# Final.net
KiCad netlist of a schematic drawn in EAGLE
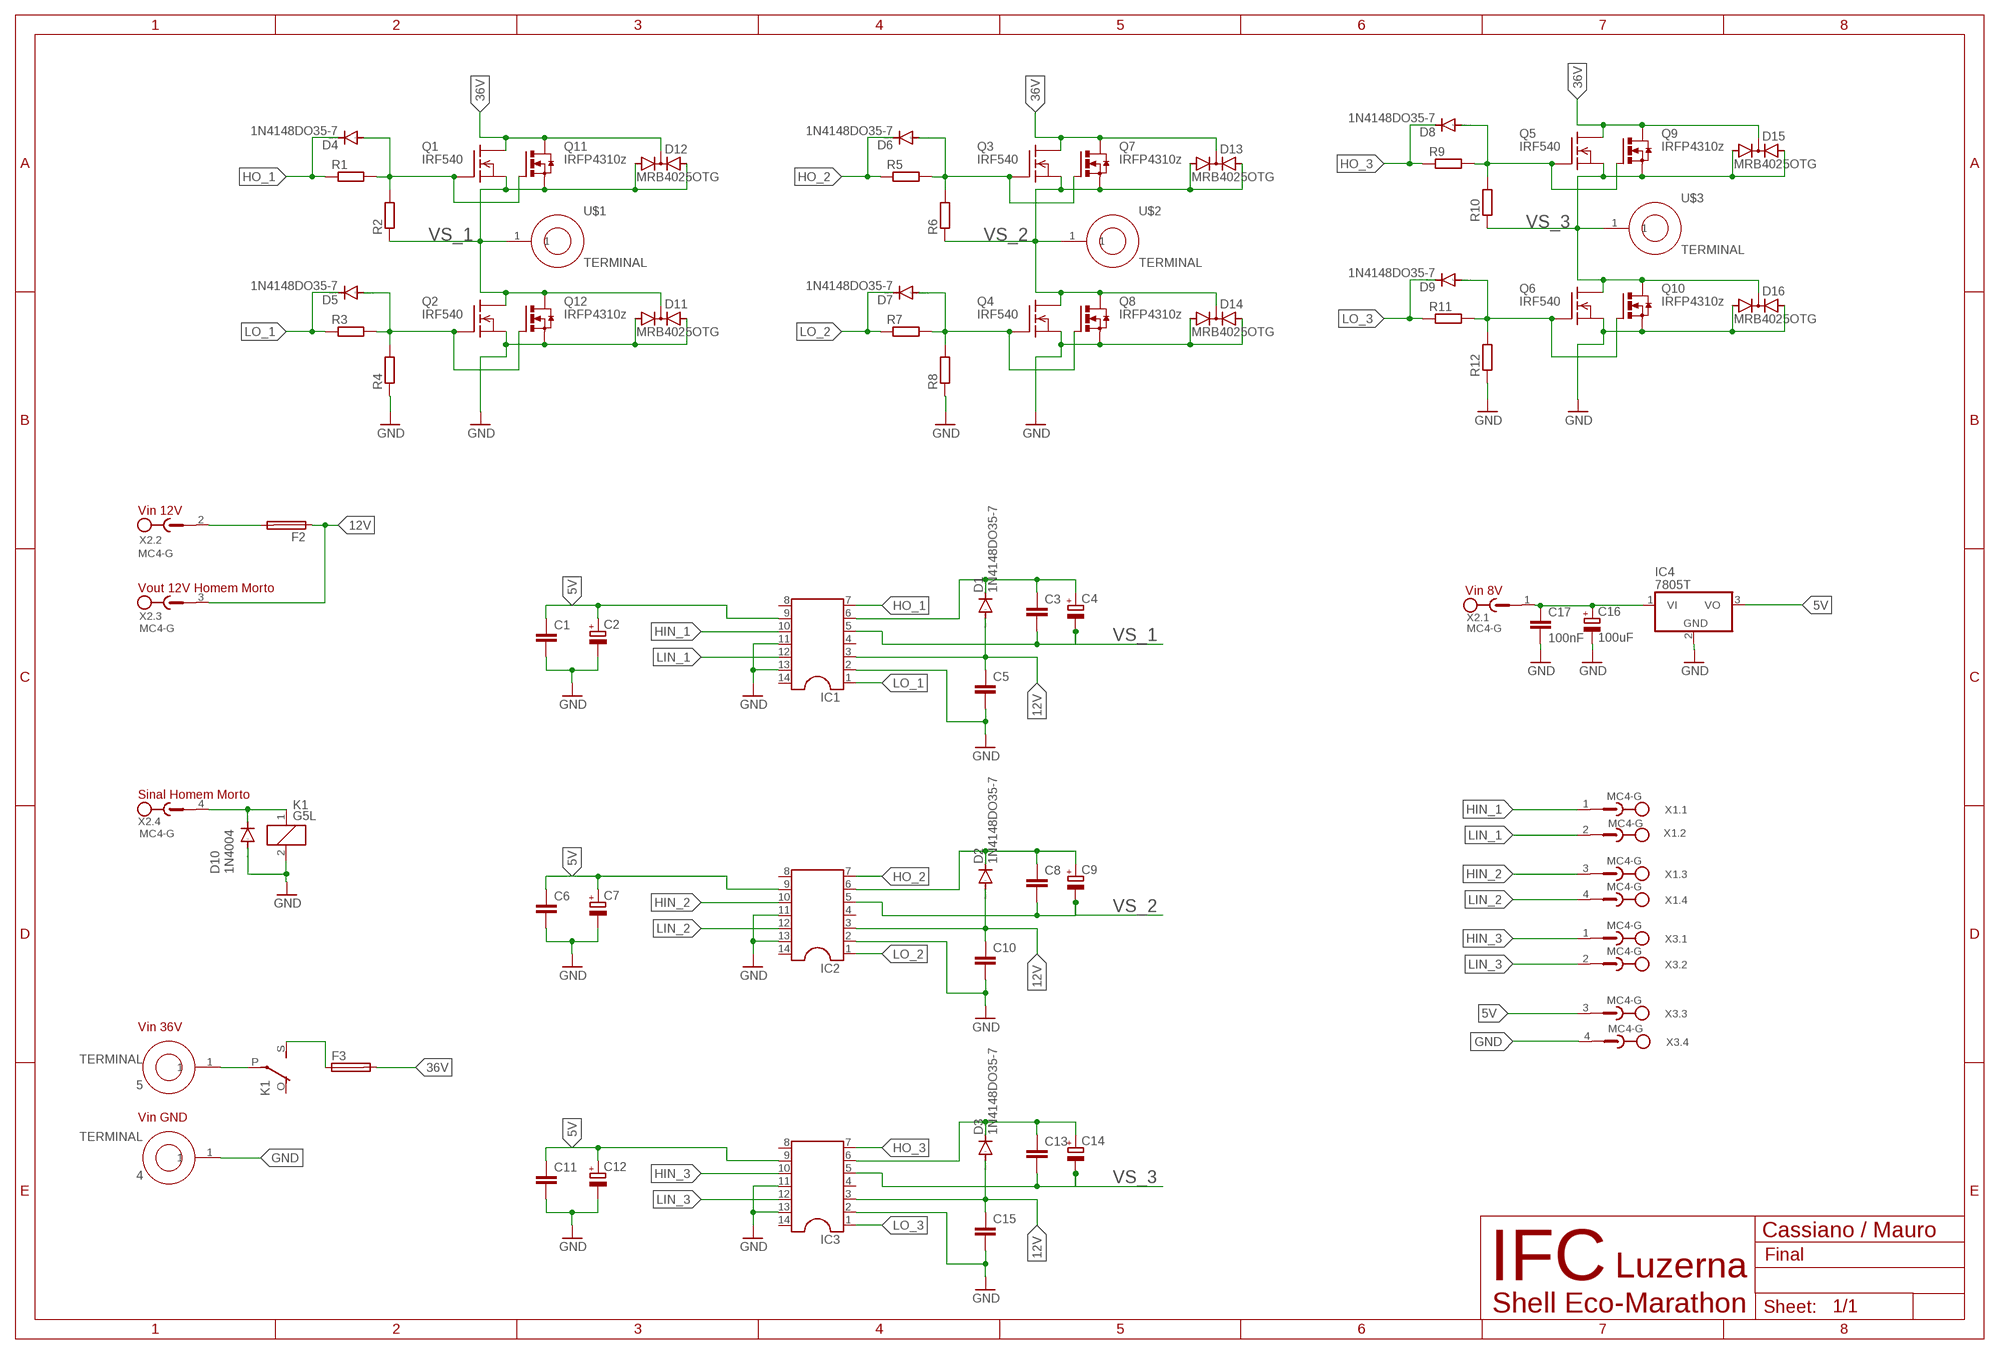
[diagram p0: schematic, sheet 1]

(export (version "E")
  (design (tool "Eeschema 10.0.6"))
  (components
    (comp (ref "4")
      (value "TERMINAL")
      (footprint "eagle-import:TERMINAL")
      (libsource (lib "eagle-import") (part "TERMINAL"))
    )
    (comp (ref "5")
      (value "TERMINAL")
      (footprint "eagle-import:TERMINAL")
      (libsource (lib "eagle-import") (part "TERMINAL"))
    )
    (comp (ref "C1")
      (value "C-EU050-045X075")
      (footprint "eagle-import:C050-045X075")
      (libsource (lib "eagle-import") (part "C-EU050-045X075"))
    )
    (comp (ref "C2")
      (value "CPOL-EUE2.5-7")
      (footprint "eagle-import:E2,5-7")
      (libsource (lib "eagle-import") (part "CPOL-EUE2.5-7"))
    )
    (comp (ref "C3")
      (value "C-EU050-025X075")
      (footprint "eagle-import:C050-025X075")
      (libsource (lib "eagle-import") (part "C-EU050-025X075"))
    )
    (comp (ref "C4")
      (value "CPOL-EUE2.5-7")
      (footprint "eagle-import:E2,5-7")
      (libsource (lib "eagle-import") (part "CPOL-EUE2.5-7"))
    )
    (comp (ref "C5")
      (value "C-EU050-025X075")
      (footprint "eagle-import:C050-025X075")
      (libsource (lib "eagle-import") (part "C-EU050-025X075"))
    )
    (comp (ref "C6")
      (value "C-EU050-045X075")
      (footprint "eagle-import:C050-045X075")
      (libsource (lib "eagle-import") (part "C-EU050-045X075"))
    )
    (comp (ref "C7")
      (value "CPOL-EUE2.5-7")
      (footprint "eagle-import:E2,5-7")
      (libsource (lib "eagle-import") (part "CPOL-EUE2.5-7"))
    )
    (comp (ref "C8")
      (value "C-EU050-025X075")
      (footprint "eagle-import:C050-025X075")
      (libsource (lib "eagle-import") (part "C-EU050-025X075"))
    )
    (comp (ref "C9")
      (value "CPOL-EUE2.5-7")
      (footprint "eagle-import:E2,5-7")
      (libsource (lib "eagle-import") (part "CPOL-EUE2.5-7"))
    )
    (comp (ref "C10")
      (value "C-EU050-025X075")
      (footprint "eagle-import:C050-025X075")
      (libsource (lib "eagle-import") (part "C-EU050-025X075"))
    )
    (comp (ref "C11")
      (value "C-EU050-045X075")
      (footprint "eagle-import:C050-045X075")
      (libsource (lib "eagle-import") (part "C-EU050-045X075"))
    )
    (comp (ref "C12")
      (value "CPOL-EUE2.5-7")
      (footprint "eagle-import:E2,5-7")
      (libsource (lib "eagle-import") (part "CPOL-EUE2.5-7"))
    )
    (comp (ref "C13")
      (value "C-EU050-025X075")
      (footprint "eagle-import:C050-025X075")
      (libsource (lib "eagle-import") (part "C-EU050-025X075"))
    )
    (comp (ref "C14")
      (value "CPOL-EUE2.5-7")
      (footprint "eagle-import:E2,5-7")
      (libsource (lib "eagle-import") (part "CPOL-EUE2.5-7"))
    )
    (comp (ref "C15")
      (value "C-EU050-025X075")
      (footprint "eagle-import:C050-025X075")
      (libsource (lib "eagle-import") (part "C-EU050-025X075"))
    )
    (comp (ref "C16")
      (value "100uF")
      (footprint "eagle-import:E2,5-7")
      (libsource (lib "eagle-import") (part "CPOL-EUE2.5-7"))
    )
    (comp (ref "C17")
      (value "100nF")
      (footprint "eagle-import:C050-045X075")
      (libsource (lib "eagle-import") (part "C-EU050-045X075"))
    )
    (comp (ref "D1")
      (value "1N4148DO35-7")
      (footprint "eagle-import:DO35-7")
      (libsource (lib "eagle-import") (part "1N4148DO35-7"))
    )
    (comp (ref "D2")
      (value "1N4148DO35-7")
      (footprint "eagle-import:DO35-7")
      (libsource (lib "eagle-import") (part "1N4148DO35-7"))
    )
    (comp (ref "D3")
      (value "1N4148DO35-7")
      (footprint "eagle-import:DO35-7")
      (libsource (lib "eagle-import") (part "1N4148DO35-7"))
    )
    (comp (ref "D4")
      (value "1N4148DO35-7")
      (footprint "eagle-import:DO35-7")
      (libsource (lib "eagle-import") (part "1N4148DO35-7"))
    )
    (comp (ref "D5")
      (value "1N4148DO35-7")
      (footprint "eagle-import:DO35-7")
      (libsource (lib "eagle-import") (part "1N4148DO35-7"))
    )
    (comp (ref "D6")
      (value "1N4148DO35-7")
      (footprint "eagle-import:DO35-7")
      (libsource (lib "eagle-import") (part "1N4148DO35-7"))
    )
    (comp (ref "D7")
      (value "1N4148DO35-7")
      (footprint "eagle-import:DO35-7")
      (libsource (lib "eagle-import") (part "1N4148DO35-7"))
    )
    (comp (ref "D8")
      (value "1N4148DO35-7")
      (footprint "eagle-import:DO35-7")
      (libsource (lib "eagle-import") (part "1N4148DO35-7"))
    )
    (comp (ref "D9")
      (value "1N4148DO35-7")
      (footprint "eagle-import:DO35-7")
      (libsource (lib "eagle-import") (part "1N4148DO35-7"))
    )
    (comp (ref "D10")
      (value "1N4004")
      (footprint "eagle-import:DO41-10")
      (libsource (lib "eagle-import") (part "1N4004"))
    )
    (comp (ref "D11")
      (value "MRB4025OTG")
      (footprint "eagle-import:TO220AB")
      (libsource (lib "eagle-import") (part "MUR620CT"))
    )
    (comp (ref "D12")
      (value "MRB4025OTG")
      (footprint "eagle-import:TO220AB")
      (libsource (lib "eagle-import") (part "MUR620CT"))
    )
    (comp (ref "D13")
      (value "MRB4025OTG")
      (footprint "eagle-import:TO220AB")
      (libsource (lib "eagle-import") (part "MUR620CT"))
    )
    (comp (ref "D14")
      (value "MRB4025OTG")
      (footprint "eagle-import:TO220AB")
      (libsource (lib "eagle-import") (part "MUR620CT"))
    )
    (comp (ref "D15")
      (value "MRB4025OTG")
      (footprint "eagle-import:TO220AB")
      (libsource (lib "eagle-import") (part "MUR620CT"))
    )
    (comp (ref "D16")
      (value "MRB4025OTG")
      (footprint "eagle-import:TO220AB")
      (libsource (lib "eagle-import") (part "MUR620CT"))
    )
    (comp (ref "F2")
      (value "SH22,5A")
      (footprint "eagle-import:SH22,5A")
      (fields (field (name "MPN") "0031.7701.11"))
      (libsource (lib "eagle-import") (part "SH22,5A"))
    )
    (comp (ref "F3")
      (value "SH22,5A")
      (footprint "eagle-import:SH22,5A")
      (fields (field (name "MPN") "0031.7701.11"))
      (libsource (lib "eagle-import") (part "SH22,5A"))
    )
    (comp (ref "IC1")
      (value "DIL14")
      (footprint "eagle-import:DIL14")
      (libsource (lib "eagle-import") (part "DIL14"))
    )
    (comp (ref "IC2")
      (value "DIL14")
      (footprint "eagle-import:DIL14")
      (libsource (lib "eagle-import") (part "DIL14"))
    )
    (comp (ref "IC3")
      (value "DIL14")
      (footprint "eagle-import:DIL14")
      (libsource (lib "eagle-import") (part "DIL14"))
    )
    (comp (ref "IC4")
      (value "7805T")
      (footprint "eagle-import:TO220H")
      (libsource (lib "eagle-import") (part "78T05"))
    )
    (comp (ref "K1")
      (value "G5L")
      (footprint "eagle-import:G5LE")
      (libsource (lib "eagle-import") (part "G5L"))
    )
    (comp (ref "Q1")
      (value "IRF540")
      (footprint "eagle-import:TO220")
      (libsource (lib "eagle-import") (part "IRF540"))
    )
    (comp (ref "Q2")
      (value "IRF540")
      (footprint "eagle-import:TO220")
      (libsource (lib "eagle-import") (part "IRF540"))
    )
    (comp (ref "Q3")
      (value "IRF540")
      (footprint "eagle-import:TO220")
      (libsource (lib "eagle-import") (part "IRF540"))
    )
    (comp (ref "Q4")
      (value "IRF540")
      (footprint "eagle-import:TO220")
      (libsource (lib "eagle-import") (part "IRF540"))
    )
    (comp (ref "Q5")
      (value "IRF540")
      (footprint "eagle-import:TO220")
      (libsource (lib "eagle-import") (part "IRF540"))
    )
    (comp (ref "Q6")
      (value "IRF540")
      (footprint "eagle-import:TO220")
      (libsource (lib "eagle-import") (part "IRF540"))
    )
    (comp (ref "Q7")
      (value "IRFP4310z")
      (footprint "eagle-import:TO247BH")
      (libsource (lib "eagle-import") (part "IRFP240-H"))
    )
    (comp (ref "Q8")
      (value "IRFP4310z")
      (footprint "eagle-import:TO247BH")
      (libsource (lib "eagle-import") (part "IRFP240-H"))
    )
    (comp (ref "Q9")
      (value "IRFP4310z")
      (footprint "eagle-import:TO247BH")
      (libsource (lib "eagle-import") (part "IRFP240-H"))
    )
    (comp (ref "Q10")
      (value "IRFP4310z")
      (footprint "eagle-import:TO247BH")
      (libsource (lib "eagle-import") (part "IRFP240-H"))
    )
    (comp (ref "Q11")
      (value "IRFP4310z")
      (footprint "eagle-import:TO247BH")
      (libsource (lib "eagle-import") (part "IRFP240-H"))
    )
    (comp (ref "Q12")
      (value "IRFP4310z")
      (footprint "eagle-import:TO247BH")
      (libsource (lib "eagle-import") (part "IRFP240-H"))
    )
    (comp (ref "R1")
      (value "R-EU_0204/7")
      (footprint "eagle-import:0204_7")
      (libsource (lib "eagle-import") (part "R-EU_0204/7"))
    )
    (comp (ref "R2")
      (value "R-EU_0204/7")
      (footprint "eagle-import:0204_7")
      (libsource (lib "eagle-import") (part "R-EU_0204/7"))
    )
    (comp (ref "R3")
      (value "R-EU_0204/7")
      (footprint "eagle-import:0204_7")
      (libsource (lib "eagle-import") (part "R-EU_0204/7"))
    )
    (comp (ref "R4")
      (value "R-EU_0204/7")
      (footprint "eagle-import:0204_7")
      (libsource (lib "eagle-import") (part "R-EU_0204/7"))
    )
    (comp (ref "R5")
      (value "R-EU_0204/7")
      (footprint "eagle-import:0204_7")
      (libsource (lib "eagle-import") (part "R-EU_0204/7"))
    )
    (comp (ref "R6")
      (value "R-EU_0204/7")
      (footprint "eagle-import:0204_7")
      (libsource (lib "eagle-import") (part "R-EU_0204/7"))
    )
    (comp (ref "R7")
      (value "R-EU_0204/7")
      (footprint "eagle-import:0204_7")
      (libsource (lib "eagle-import") (part "R-EU_0204/7"))
    )
    (comp (ref "R8")
      (value "R-EU_0204/7")
      (footprint "eagle-import:0204_7")
      (libsource (lib "eagle-import") (part "R-EU_0204/7"))
    )
    (comp (ref "R9")
      (value "R-EU_0204/7")
      (footprint "eagle-import:0204_7")
      (libsource (lib "eagle-import") (part "R-EU_0204/7"))
    )
    (comp (ref "R10")
      (value "R-EU_0204/7")
      (footprint "eagle-import:0204_7")
      (libsource (lib "eagle-import") (part "R-EU_0204/7"))
    )
    (comp (ref "R11")
      (value "R-EU_0204/7")
      (footprint "eagle-import:0204_7")
      (libsource (lib "eagle-import") (part "R-EU_0204/7"))
    )
    (comp (ref "R12")
      (value "R-EU_0204/7")
      (footprint "eagle-import:0204_7")
      (libsource (lib "eagle-import") (part "R-EU_0204/7"))
    )
    (comp (ref "U$1")
      (value "TERMINAL")
      (footprint "eagle-import:TERMINAL")
      (libsource (lib "eagle-import") (part "TERMINAL"))
    )
    (comp (ref "U$2")
      (value "TERMINAL")
      (footprint "eagle-import:TERMINAL")
      (libsource (lib "eagle-import") (part "TERMINAL"))
    )
    (comp (ref "U$3")
      (value "TERMINAL")
      (footprint "eagle-import:TERMINAL")
      (libsource (lib "eagle-import") (part "TERMINAL"))
    )
    (comp (ref "X1")
      (value "MC4-G")
      (footprint "eagle-import:MC4-G")
      (libsource (lib "eagle-import") (part "MC4-G"))
    )
    (comp (ref "X2")
      (value "MC4-G")
      (footprint "eagle-import:MC4-G")
      (libsource (lib "eagle-import") (part "MC4-G"))
    )
    (comp (ref "X3")
      (value "MC4-G")
      (footprint "eagle-import:MC4-G")
      (libsource (lib "eagle-import") (part "MC4-G"))
    )
  )
  (nets
    (net (code "1") (name "/VS_1") (class "Default")
      (node (ref "C3") (pin "2") (pinfunction "2_2") (pintype "passive"))
      (node (ref "C4") (pin "-") (pinfunction "-_-") (pintype "passive"))
      (node (ref "D11") (pin "C") (pinfunction "C_C") (pintype "passive"))
      (node (ref "D12") (pin "A1") (pinfunction "A1_A1") (pintype "passive"))
      (node (ref "D12") (pin "A2") (pinfunction "A2_A2") (pintype "passive"))
      (node (ref "IC1") (pin "5") (pinfunction "5_5") (pintype "passive"))
      (node (ref "Q1") (pin "3") (pinfunction "S_3") (pintype "passive"))
      (node (ref "Q11") (pin "S") (pinfunction "S_S") (pintype "passive"))
      (node (ref "Q12") (pin "D") (pinfunction "D_D") (pintype "passive"))
      (node (ref "Q2") (pin "2") (pinfunction "D_2") (pintype "passive"))
      (node (ref "R2") (pin "1") (pinfunction "1_1") (pintype "passive"))
      (node (ref "U$1") (pin "1") (pinfunction "1_1") (pintype "bidirectional"))
    )
    (net (code "2") (name "/VS_2") (class "Default")
      (node (ref "C8") (pin "2") (pinfunction "2_2") (pintype "passive"))
      (node (ref "C9") (pin "-") (pinfunction "-_-") (pintype "passive"))
      (node (ref "D13") (pin "A1") (pinfunction "A1_A1") (pintype "passive"))
      (node (ref "D13") (pin "A2") (pinfunction "A2_A2") (pintype "passive"))
      (node (ref "D14") (pin "C") (pinfunction "C_C") (pintype "passive"))
      (node (ref "IC2") (pin "5") (pinfunction "5_5") (pintype "passive"))
      (node (ref "Q3") (pin "3") (pinfunction "S_3") (pintype "passive"))
      (node (ref "Q4") (pin "2") (pinfunction "D_2") (pintype "passive"))
      (node (ref "Q7") (pin "S") (pinfunction "S_S") (pintype "passive"))
      (node (ref "Q8") (pin "D") (pinfunction "D_D") (pintype "passive"))
      (node (ref "R6") (pin "1") (pinfunction "1_1") (pintype "passive"))
      (node (ref "U$2") (pin "1") (pinfunction "1_1") (pintype "bidirectional"))
    )
    (net (code "3") (name "/VS_3") (class "Default")
      (node (ref "C13") (pin "2") (pinfunction "2_2") (pintype "passive"))
      (node (ref "C14") (pin "-") (pinfunction "-_-") (pintype "passive"))
      (node (ref "D15") (pin "A1") (pinfunction "A1_A1") (pintype "passive"))
      (node (ref "D15") (pin "A2") (pinfunction "A2_A2") (pintype "passive"))
      (node (ref "D16") (pin "C") (pinfunction "C_C") (pintype "passive"))
      (node (ref "IC3") (pin "5") (pinfunction "5_5") (pintype "passive"))
      (node (ref "Q10") (pin "D") (pinfunction "D_D") (pintype "passive"))
      (node (ref "Q5") (pin "3") (pinfunction "S_3") (pintype "passive"))
      (node (ref "Q6") (pin "2") (pinfunction "D_2") (pintype "passive"))
      (node (ref "Q9") (pin "S") (pinfunction "S_S") (pintype "passive"))
      (node (ref "R10") (pin "1") (pinfunction "1_1") (pintype "passive"))
      (node (ref "U$3") (pin "1") (pinfunction "1_1") (pintype "bidirectional"))
    )
    (net (code "4") (name "5V") (class "Default")
      (node (ref "C1") (pin "1") (pinfunction "1_1") (pintype "passive"))
      (node (ref "C11") (pin "1") (pinfunction "1_1") (pintype "passive"))
      (node (ref "C12") (pin "+") (pinfunction "+_+") (pintype "passive"))
      (node (ref "C2") (pin "+") (pinfunction "+_+") (pintype "passive"))
      (node (ref "C6") (pin "1") (pinfunction "1_1") (pintype "passive"))
      (node (ref "C7") (pin "+") (pinfunction "+_+") (pintype "passive"))
      (node (ref "IC1") (pin "9") (pinfunction "9_9") (pintype "passive"))
      (node (ref "IC2") (pin "9") (pinfunction "9_9") (pintype "passive"))
      (node (ref "IC3") (pin "9") (pinfunction "9_9") (pintype "passive"))
      (node (ref "IC4") (pin "3") (pinfunction "VO_3") (pintype "passive"))
      (node (ref "X3") (pin "3") (pinfunction "SK_3") (pintype "passive"))
    )
    (net (code "5") (name "12V") (class "Default")
      (node (ref "C10") (pin "1") (pinfunction "1_1") (pintype "passive"))
      (node (ref "C15") (pin "1") (pinfunction "1_1") (pintype "passive"))
      (node (ref "C5") (pin "1") (pinfunction "1_1") (pintype "passive"))
      (node (ref "D1") (pin "A") (pinfunction "A_A") (pintype "passive"))
      (node (ref "D2") (pin "A") (pinfunction "A_A") (pintype "passive"))
      (node (ref "D3") (pin "A") (pinfunction "A_A") (pintype "passive"))
      (node (ref "F2") (pin "1") (pinfunction "1_1") (pintype "passive"))
      (node (ref "IC1") (pin "3") (pinfunction "3_3") (pintype "passive"))
      (node (ref "IC2") (pin "3") (pinfunction "3_3") (pintype "passive"))
      (node (ref "IC3") (pin "3") (pinfunction "3_3") (pintype "passive"))
      (node (ref "X2") (pin "3") (pinfunction "SK_3") (pintype "passive"))
    )
    (net (code "6") (name "36V") (class "Default")
      (node (ref "D12") (pin "C") (pinfunction "C_C") (pintype "passive"))
      (node (ref "D13") (pin "C") (pinfunction "C_C") (pintype "passive"))
      (node (ref "D15") (pin "C") (pinfunction "C_C") (pintype "passive"))
      (node (ref "F3") (pin "2") (pinfunction "2_2") (pintype "passive"))
      (node (ref "Q1") (pin "2") (pinfunction "D_2") (pintype "passive"))
      (node (ref "Q11") (pin "D") (pinfunction "D_D") (pintype "passive"))
      (node (ref "Q3") (pin "2") (pinfunction "D_2") (pintype "passive"))
      (node (ref "Q5") (pin "2") (pinfunction "D_2") (pintype "passive"))
      (node (ref "Q7") (pin "D") (pinfunction "D_D") (pintype "passive"))
      (node (ref "Q9") (pin "D") (pinfunction "D_D") (pintype "passive"))
    )
    (net (code "7") (name "GND") (class "Default")
      (node (ref "4") (pin "1") (pinfunction "1_1") (pintype "bidirectional"))
      (node (ref "C1") (pin "2") (pinfunction "2_2") (pintype "passive"))
      (node (ref "C10") (pin "2") (pinfunction "2_2") (pintype "passive"))
      (node (ref "C11") (pin "2") (pinfunction "2_2") (pintype "passive"))
      (node (ref "C12") (pin "-") (pinfunction "-_-") (pintype "passive"))
      (node (ref "C15") (pin "2") (pinfunction "2_2") (pintype "passive"))
      (node (ref "C16") (pin "-") (pinfunction "-_-") (pintype "passive"))
      (node (ref "C17") (pin "2") (pinfunction "2_2") (pintype "passive"))
      (node (ref "C2") (pin "-") (pinfunction "-_-") (pintype "passive"))
      (node (ref "C5") (pin "2") (pinfunction "2_2") (pintype "passive"))
      (node (ref "C6") (pin "2") (pinfunction "2_2") (pintype "passive"))
      (node (ref "C7") (pin "-") (pinfunction "-_-") (pintype "passive"))
      (node (ref "D10") (pin "A") (pinfunction "A_A") (pintype "passive"))
      (node (ref "D11") (pin "A1") (pinfunction "A1_A1") (pintype "passive"))
      (node (ref "D11") (pin "A2") (pinfunction "A2_A2") (pintype "passive"))
      (node (ref "D14") (pin "A1") (pinfunction "A1_A1") (pintype "passive"))
      (node (ref "D14") (pin "A2") (pinfunction "A2_A2") (pintype "passive"))
      (node (ref "D16") (pin "A1") (pinfunction "A1_A1") (pintype "passive"))
      (node (ref "D16") (pin "A2") (pinfunction "A2_A2") (pintype "passive"))
      (node (ref "IC1") (pin "11") (pinfunction "11_11") (pintype "passive"))
      (node (ref "IC1") (pin "13") (pinfunction "13_13") (pintype "passive"))
      (node (ref "IC1") (pin "2") (pinfunction "2_2") (pintype "passive"))
      (node (ref "IC2") (pin "11") (pinfunction "11_11") (pintype "passive"))
      (node (ref "IC2") (pin "13") (pinfunction "13_13") (pintype "passive"))
      (node (ref "IC2") (pin "2") (pinfunction "2_2") (pintype "passive"))
      (node (ref "IC3") (pin "11") (pinfunction "11_11") (pintype "passive"))
      (node (ref "IC3") (pin "13") (pinfunction "13_13") (pintype "passive"))
      (node (ref "IC3") (pin "2") (pinfunction "2_2") (pintype "passive"))
      (node (ref "IC4") (pin "2") (pinfunction "GND_2") (pintype "passive"))
      (node (ref "K1") (pin "2") (pinfunction "2_2") (pintype "passive"))
      (node (ref "Q10") (pin "S") (pinfunction "S_S") (pintype "passive"))
      (node (ref "Q12") (pin "S") (pinfunction "S_S") (pintype "passive"))
      (node (ref "Q2") (pin "3") (pinfunction "S_3") (pintype "passive"))
      (node (ref "Q4") (pin "3") (pinfunction "S_3") (pintype "passive"))
      (node (ref "Q6") (pin "3") (pinfunction "S_3") (pintype "passive"))
      (node (ref "Q8") (pin "S") (pinfunction "S_S") (pintype "passive"))
      (node (ref "R12") (pin "1") (pinfunction "1_1") (pintype "passive"))
      (node (ref "R4") (pin "1") (pinfunction "1_1") (pintype "passive"))
      (node (ref "R8") (pin "1") (pinfunction "1_1") (pintype "passive"))
      (node (ref "X3") (pin "4") (pinfunction "SK_4") (pintype "passive"))
    )
    (net (code "8") (name "HIN_1") (class "Default")
      (node (ref "IC1") (pin "10") (pinfunction "10_10") (pintype "passive"))
      (node (ref "X1") (pin "1") (pinfunction "SK_1") (pintype "passive"))
    )
    (net (code "9") (name "HIN_2") (class "Default")
      (node (ref "IC2") (pin "10") (pinfunction "10_10") (pintype "passive"))
      (node (ref "X1") (pin "3") (pinfunction "SK_3") (pintype "passive"))
    )
    (net (code "10") (name "HIN_3") (class "Default")
      (node (ref "IC3") (pin "10") (pinfunction "10_10") (pintype "passive"))
      (node (ref "X3") (pin "1") (pinfunction "SK_1") (pintype "passive"))
    )
    (net (code "11") (name "HO_1") (class "Default")
      (node (ref "D4") (pin "C") (pinfunction "C_C") (pintype "passive"))
      (node (ref "IC1") (pin "7") (pinfunction "7_7") (pintype "passive"))
      (node (ref "R1") (pin "1") (pinfunction "1_1") (pintype "passive"))
    )
    (net (code "12") (name "HO_2") (class "Default")
      (node (ref "D6") (pin "C") (pinfunction "C_C") (pintype "passive"))
      (node (ref "IC2") (pin "7") (pinfunction "7_7") (pintype "passive"))
      (node (ref "R5") (pin "1") (pinfunction "1_1") (pintype "passive"))
    )
    (net (code "13") (name "HO_3") (class "Default")
      (node (ref "D8") (pin "C") (pinfunction "C_C") (pintype "passive"))
      (node (ref "IC3") (pin "7") (pinfunction "7_7") (pintype "passive"))
      (node (ref "R9") (pin "1") (pinfunction "1_1") (pintype "passive"))
    )
    (net (code "14") (name "LIN_1") (class "Default")
      (node (ref "IC1") (pin "12") (pinfunction "12_12") (pintype "passive"))
      (node (ref "X1") (pin "2") (pinfunction "SK_2") (pintype "passive"))
    )
    (net (code "15") (name "LIN_2") (class "Default")
      (node (ref "IC2") (pin "12") (pinfunction "12_12") (pintype "passive"))
      (node (ref "X1") (pin "4") (pinfunction "SK_4") (pintype "passive"))
    )
    (net (code "16") (name "LIN_3") (class "Default")
      (node (ref "IC3") (pin "12") (pinfunction "12_12") (pintype "passive"))
      (node (ref "X3") (pin "2") (pinfunction "SK_2") (pintype "passive"))
    )
    (net (code "17") (name "LO_1") (class "Default")
      (node (ref "D5") (pin "C") (pinfunction "C_C") (pintype "passive"))
      (node (ref "IC1") (pin "1") (pinfunction "1_1") (pintype "passive"))
      (node (ref "R3") (pin "1") (pinfunction "1_1") (pintype "passive"))
    )
    (net (code "18") (name "LO_2") (class "Default")
      (node (ref "D7") (pin "C") (pinfunction "C_C") (pintype "passive"))
      (node (ref "IC2") (pin "1") (pinfunction "1_1") (pintype "passive"))
      (node (ref "R7") (pin "1") (pinfunction "1_1") (pintype "passive"))
    )
    (net (code "19") (name "LO_3") (class "Default")
      (node (ref "D9") (pin "C") (pinfunction "C_C") (pintype "passive"))
      (node (ref "IC3") (pin "1") (pinfunction "1_1") (pintype "passive"))
      (node (ref "R11") (pin "1") (pinfunction "1_1") (pintype "passive"))
    )
    (net (code "20") (name "Net-(5-Pad1)") (class "Default")
      (node (ref "5") (pin "1") (pinfunction "1_1") (pintype "bidirectional"))
      (node (ref "K1") (pin "P") (pinfunction "P_P") (pintype "passive"))
    )
    (net (code "21") (name "Net-(C3-Pad1)") (class "Default")
      (node (ref "C3") (pin "1") (pinfunction "1_1") (pintype "passive"))
      (node (ref "C4") (pin "+") (pinfunction "+_+") (pintype "passive"))
      (node (ref "D1") (pin "C") (pinfunction "C_C") (pintype "passive"))
      (node (ref "IC1") (pin "6") (pinfunction "6_6") (pintype "passive"))
    )
    (net (code "22") (name "Net-(C8-Pad1)") (class "Default")
      (node (ref "C8") (pin "1") (pinfunction "1_1") (pintype "passive"))
      (node (ref "C9") (pin "+") (pinfunction "+_+") (pintype "passive"))
      (node (ref "D2") (pin "C") (pinfunction "C_C") (pintype "passive"))
      (node (ref "IC2") (pin "6") (pinfunction "6_6") (pintype "passive"))
    )
    (net (code "23") (name "Net-(C13-Pad1)") (class "Default")
      (node (ref "C13") (pin "1") (pinfunction "1_1") (pintype "passive"))
      (node (ref "C14") (pin "+") (pinfunction "+_+") (pintype "passive"))
      (node (ref "D3") (pin "C") (pinfunction "C_C") (pintype "passive"))
      (node (ref "IC3") (pin "6") (pinfunction "6_6") (pintype "passive"))
    )
    (net (code "24") (name "Net-(F3-Pad1)") (class "Default")
      (node (ref "F3") (pin "1") (pinfunction "1_1") (pintype "passive"))
      (node (ref "K1") (pin "S") (pinfunction "S_S") (pintype "passive"))
    )
    (net (code "25") (name "Net-(IC4-VI)") (class "Default")
      (node (ref "C16") (pin "+") (pinfunction "+_+") (pintype "passive"))
      (node (ref "C17") (pin "1") (pinfunction "1_1") (pintype "passive"))
      (node (ref "IC4") (pin "1") (pinfunction "VI_1") (pintype "input"))
      (node (ref "X2") (pin "1") (pinfunction "SK_1") (pintype "passive"))
    )
    (net (code "26") (name "Net-(Q1-G)") (class "Default")
      (node (ref "D4") (pin "A") (pinfunction "A_A") (pintype "passive"))
      (node (ref "Q1") (pin "1") (pinfunction "G_1") (pintype "passive"))
      (node (ref "Q11") (pin "G") (pinfunction "G_G") (pintype "passive"))
      (node (ref "R1") (pin "2") (pinfunction "2_2") (pintype "passive"))
      (node (ref "R2") (pin "2") (pinfunction "2_2") (pintype "passive"))
    )
    (net (code "27") (name "Net-(Q2-G)") (class "Default")
      (node (ref "D5") (pin "A") (pinfunction "A_A") (pintype "passive"))
      (node (ref "Q12") (pin "G") (pinfunction "G_G") (pintype "passive"))
      (node (ref "Q2") (pin "1") (pinfunction "G_1") (pintype "passive"))
      (node (ref "R3") (pin "2") (pinfunction "2_2") (pintype "passive"))
      (node (ref "R4") (pin "2") (pinfunction "2_2") (pintype "passive"))
    )
    (net (code "28") (name "Net-(Q3-G)") (class "Default")
      (node (ref "D6") (pin "A") (pinfunction "A_A") (pintype "passive"))
      (node (ref "Q3") (pin "1") (pinfunction "G_1") (pintype "passive"))
      (node (ref "Q7") (pin "G") (pinfunction "G_G") (pintype "passive"))
      (node (ref "R5") (pin "2") (pinfunction "2_2") (pintype "passive"))
      (node (ref "R6") (pin "2") (pinfunction "2_2") (pintype "passive"))
    )
    (net (code "29") (name "Net-(Q4-G)") (class "Default")
      (node (ref "D7") (pin "A") (pinfunction "A_A") (pintype "passive"))
      (node (ref "Q4") (pin "1") (pinfunction "G_1") (pintype "passive"))
      (node (ref "Q8") (pin "G") (pinfunction "G_G") (pintype "passive"))
      (node (ref "R7") (pin "2") (pinfunction "2_2") (pintype "passive"))
      (node (ref "R8") (pin "2") (pinfunction "2_2") (pintype "passive"))
    )
    (net (code "30") (name "Net-(Q5-G)") (class "Default")
      (node (ref "D8") (pin "A") (pinfunction "A_A") (pintype "passive"))
      (node (ref "Q5") (pin "1") (pinfunction "G_1") (pintype "passive"))
      (node (ref "Q9") (pin "G") (pinfunction "G_G") (pintype "passive"))
      (node (ref "R10") (pin "2") (pinfunction "2_2") (pintype "passive"))
      (node (ref "R9") (pin "2") (pinfunction "2_2") (pintype "passive"))
    )
    (net (code "31") (name "Net-(Q6-G)") (class "Default")
      (node (ref "D9") (pin "A") (pinfunction "A_A") (pintype "passive"))
      (node (ref "Q10") (pin "G") (pinfunction "G_G") (pintype "passive"))
      (node (ref "Q6") (pin "1") (pinfunction "G_1") (pintype "passive"))
      (node (ref "R11") (pin "2") (pinfunction "2_2") (pintype "passive"))
      (node (ref "R12") (pin "2") (pinfunction "2_2") (pintype "passive"))
    )
    (net (code "32") (name "Net-(X2B-SK)") (class "Default")
      (node (ref "F2") (pin "2") (pinfunction "2_2") (pintype "passive"))
      (node (ref "X2") (pin "2") (pinfunction "SK_2") (pintype "passive"))
    )
    (net (code "33") (name "Net-(X2D-SK)") (class "Default")
      (node (ref "D10") (pin "C") (pinfunction "C_C") (pintype "passive"))
      (node (ref "K1") (pin "1") (pinfunction "1_1") (pintype "passive"))
      (node (ref "X2") (pin "4") (pinfunction "SK_4") (pintype "passive"))
    )
    (net (code "34") (name "unconnected-(IC1-Pad4)") (class "Default")
      (node (ref "IC1") (pin "4") (pinfunction "4_4") (pintype "passive"))
    )
    (net (code "35") (name "unconnected-(IC1-Pad8)") (class "Default")
      (node (ref "IC1") (pin "8") (pinfunction "8_8") (pintype "passive"))
    )
    (net (code "36") (name "unconnected-(IC1-Pad14)") (class "Default")
      (node (ref "IC1") (pin "14") (pinfunction "14_14") (pintype "passive"))
    )
    (net (code "37") (name "unconnected-(IC2-Pad4)") (class "Default")
      (node (ref "IC2") (pin "4") (pinfunction "4_4") (pintype "passive"))
    )
    (net (code "38") (name "unconnected-(IC2-Pad8)") (class "Default")
      (node (ref "IC2") (pin "8") (pinfunction "8_8") (pintype "passive"))
    )
    (net (code "39") (name "unconnected-(IC2-Pad14)") (class "Default")
      (node (ref "IC2") (pin "14") (pinfunction "14_14") (pintype "passive"))
    )
    (net (code "40") (name "unconnected-(IC3-Pad4)") (class "Default")
      (node (ref "IC3") (pin "4") (pinfunction "4_4") (pintype "passive"))
    )
    (net (code "41") (name "unconnected-(IC3-Pad8)") (class "Default")
      (node (ref "IC3") (pin "8") (pinfunction "8_8") (pintype "passive"))
    )
    (net (code "42") (name "unconnected-(IC3-Pad14)") (class "Default")
      (node (ref "IC3") (pin "14") (pinfunction "14_14") (pintype "passive"))
    )
    (net (code "43") (name "unconnected-(K1-PadO)") (class "Default")
      (node (ref "K1") (pin "O") (pinfunction "O_O") (pintype "passive"))
    )
  )
)
